# Quadcopter.net
KiCad netlist of a schematic drawn in Altium Designer
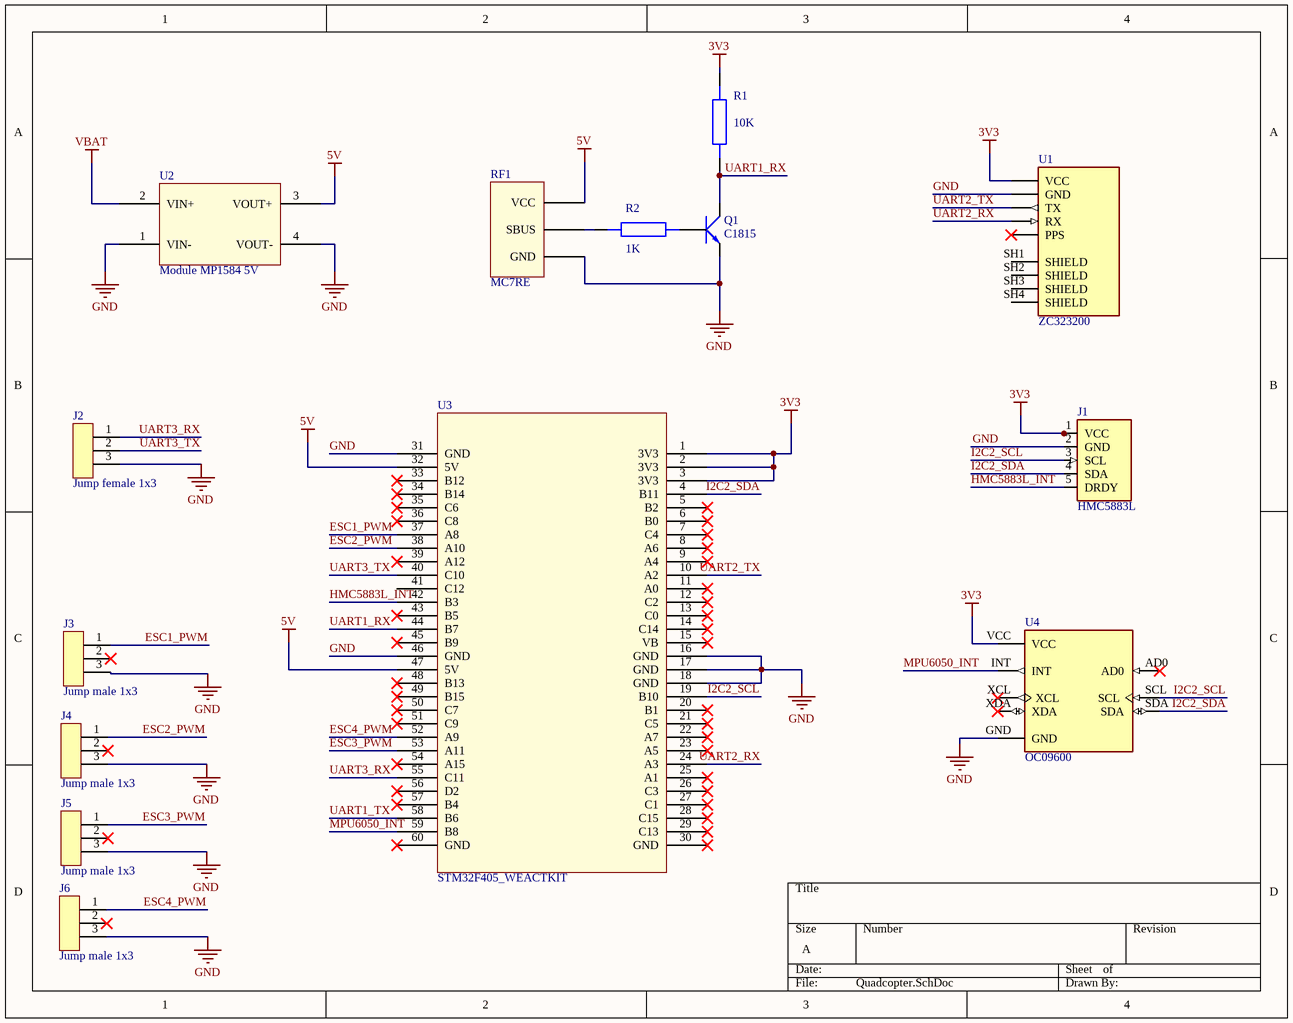
[diagram p0: Quadcopter.SchDoc]

(export (version "E")
  (design (tool "Eeschema 10.0.6"))
  (components
    (comp (ref "J1")
      (value "HMC5883L")
      (footprint "HMC5883L")
      (description "Magnetic Sensor Development Tools 3-Axis Digital Compass w 12-Bit ADC")
      (fields (field (name "MF") "STMicroelectronics"))
      (libsource (lib "Schlib1") (part "HMC5883L"))
    )
    (comp (ref "J2")
      (value "Jump female 1x3")
      (footprint "FEMALE JUMP 1X3")
      (libsource (lib "Schlib1") (part "Jump female 1x3"))
    )
    (comp (ref "J3")
      (value "Jump male 1x3")
      (footprint "FEMALE JUMP 1X3")
      (libsource (lib "Schlib1") (part "Jump male 1x3"))
    )
    (comp (ref "J4")
      (value "Jump male 1x3")
      (footprint "FEMALE JUMP 1X3")
      (libsource (lib "Schlib1") (part "Jump male 1x3"))
    )
    (comp (ref "J5")
      (value "Jump male 1x3")
      (footprint "FEMALE JUMP 1X3")
      (libsource (lib "Schlib1") (part "Jump male 1x3"))
    )
    (comp (ref "J6")
      (value "Jump male 1x3")
      (footprint "FEMALE JUMP 1X3")
      (libsource (lib "Schlib1") (part "Jump male 1x3"))
    )
    (comp (ref "Q1")
      (value "C1815")
      (footprint "TO92127P508H508-3")
      (description "NPN transistor")
      (libsource (lib "Schlib1") (part "Trans C1815 DIP"))
    )
    (comp (ref "R1") (value "10K") (footprint "Tro Vach 1/4W") (libsource (lib "Schlib1") (part "RES")))
    (comp (ref "R2") (value "1K") (footprint "Tro Vach 1/4W") (libsource (lib "Schlib1") (part "RES")))
    (comp (ref "RF1") (value "MC7RE") (footprint "RECEIVER") (libsource (lib "Schlib1") (part "RECEIVER")))
    (comp (ref "U1")
      (value "ZC323200")
      (footprint "GPS_NEO")
      (description "GY-NEO6MV2 GY-GPS6MV2 NEO-6M GPS Module with Flight Control APM2.5")
      (fields (field (name "MF") "YKS"))
      (libsource (lib "Schlib1") (part "ZC323200"))
    )
    (comp (ref "U2")
      (value "Module MP1584 5V")
      (footprint "MODULE_MP1584")
      (libsource (lib "Schlib1") (part "Module MP1584 5V"))
    )
    (comp (ref "U3")
      (value "STM32F405_WEACTKIT")
      (footprint "STM32F405RGT6 - WEACT kit")
      (libsource (lib "Schlib1") (part "STM32F405_WEACTKIT"))
    )
    (comp (ref "U4")
      (value "OC09600")
      (footprint "MODULE_MPU6050")
      (description "GY-521 6 DOF MPU-6050 Module 3 Axis Accelerometer Gyroscope Module for Arduino")
      (fields (field (name "MF") "YKS"))
      (libsource (lib "Schlib1") (part "OC09600"))
    )
  )
  (nets
    (net (code "2") (name "/ESC1_PWM") (class "Default")
      (node (ref "J3") (pin "1") (pintype "passive"))
      (node (ref "U3") (pin "37") (pinfunction "A8_37") (pintype "passive"))
    )
    (net (code "3") (name "/ESC2_PWM") (class "Default")
      (node (ref "J4") (pin "1") (pintype "passive"))
      (node (ref "U3") (pin "38") (pinfunction "A10_38") (pintype "passive"))
    )
    (net (code "4") (name "/ESC3_PWM") (class "Default")
      (node (ref "J5") (pin "1") (pintype "passive"))
      (node (ref "U3") (pin "53") (pinfunction "A11_53") (pintype "passive"))
    )
    (net (code "5") (name "/ESC4_PWM") (class "Default")
      (node (ref "J6") (pin "1") (pintype "passive"))
      (node (ref "U3") (pin "52") (pinfunction "A9_52") (pintype "passive"))
    )
    (net (code "6") (name "/HMC5883L_INT") (class "Default")
      (node (ref "J1") (pin "5") (pinfunction "DRDY_5") (pintype "bidirectional"))
      (node (ref "U3") (pin "42") (pinfunction "B3_42") (pintype "passive"))
    )
    (net (code "7") (name "/I2C2_SCL") (class "Default")
      (node (ref "J1") (pin "3") (pinfunction "SCL_3") (pintype "input"))
      (node (ref "U3") (pin "19") (pinfunction "B10_19") (pintype "passive"))
      (node (ref "U4") (pin "SCL") (pinfunction "SCL_SCL") (pintype "input"))
    )
    (net (code "8") (name "/I2C2_SDA") (class "Default")
      (node (ref "J1") (pin "4") (pinfunction "SDA_4") (pintype "bidirectional"))
      (node (ref "U3") (pin "4") (pinfunction "B11_4") (pintype "passive"))
      (node (ref "U4") (pin "SDA") (pinfunction "SDA_SDA") (pintype "bidirectional"))
    )
    (net (code "9") (name "/MPU6050_INT") (class "Default")
      (node (ref "U3") (pin "59") (pinfunction "B8_59") (pintype "passive"))
      (node (ref "U4") (pin "INT") (pinfunction "INT_INT") (pintype "output"))
    )
    (net (code "10") (name "/UART1_RX") (class "Default")
      (node (ref "Q1") (pin "2") (pinfunction "C_2") (pintype "passive"))
      (node (ref "R1") (pin "1") (pinfunction "1_1") (pintype "passive"))
      (node (ref "U3") (pin "44") (pinfunction "B7_44") (pintype "passive"))
    )
    (net (code "11") (name "/UART1_TX") (class "Default")
      (node (ref "U3") (pin "58") (pinfunction "B6_58") (pintype "passive"))
    )
    (net (code "12") (name "/UART2_RX") (class "Default")
      (node (ref "U1") (pin "2") (pinfunction "RX_2") (pintype "input"))
      (node (ref "U3") (pin "24") (pinfunction "A3_24") (pintype "passive"))
    )
    (net (code "13") (name "/UART2_TX") (class "Default")
      (node (ref "U1") (pin "3") (pinfunction "TX_3") (pintype "output"))
      (node (ref "U3") (pin "10") (pinfunction "A2_10") (pintype "passive"))
    )
    (net (code "14") (name "/UART3_RX") (class "Default")
      (node (ref "J2") (pin "1") (pintype "passive"))
      (node (ref "U3") (pin "55") (pinfunction "C11_55") (pintype "passive"))
    )
    (net (code "15") (name "/UART3_TX") (class "Default")
      (node (ref "J2") (pin "2") (pintype "passive"))
      (node (ref "U3") (pin "40") (pinfunction "C10_40") (pintype "passive"))
    )
    (net (code "16") (name "3V3") (class "Default")
      (node (ref "J1") (pin "1") (pinfunction "VCC_1") (pintype "power_in"))
      (node (ref "R1") (pin "2") (pinfunction "2_2") (pintype "passive"))
      (node (ref "U1") (pin "5") (pinfunction "VCC_5") (pintype "power_in"))
      (node (ref "U3") (pin "1") (pinfunction "3V3_1") (pintype "passive"))
      (node (ref "U3") (pin "2") (pinfunction "3V3_2") (pintype "passive"))
      (node (ref "U3") (pin "3") (pinfunction "3V3_3") (pintype "passive"))
      (node (ref "U4") (pin "VCC") (pinfunction "VCC_VCC") (pintype "power_in"))
    )
    (net (code "17") (name "5V") (class "Default")
      (node (ref "RF1") (pin "5V") (pinfunction "VCC_5V") (pintype "passive"))
      (node (ref "U2") (pin "3") (pinfunction "VOUT+_3") (pintype "passive"))
      (node (ref "U3") (pin "32") (pinfunction "5V_32") (pintype "passive"))
      (node (ref "U3") (pin "47") (pinfunction "5V_47") (pintype "passive"))
    )
    (net (code "18") (name "GND") (class "Default")
      (node (ref "J1") (pin "2") (pinfunction "GND_2") (pintype "power_in"))
      (node (ref "J2") (pin "3") (pintype "passive"))
      (node (ref "J3") (pin "3") (pintype "passive"))
      (node (ref "J4") (pin "3") (pintype "passive"))
      (node (ref "J5") (pin "3") (pintype "passive"))
      (node (ref "J6") (pin "3") (pintype "passive"))
      (node (ref "Q1") (pin "1") (pinfunction "E_1") (pintype "passive"))
      (node (ref "RF1") (pin "GND") (pinfunction "GND_GND") (pintype "passive"))
      (node (ref "U1") (pin "4") (pinfunction "GND_4") (pintype "power_in"))
      (node (ref "U2") (pin "1") (pinfunction "VIN-_1") (pintype "passive"))
      (node (ref "U2") (pin "4") (pinfunction "VOUT-_4") (pintype "passive"))
      (node (ref "U3") (pin "16") (pinfunction "GND_16") (pintype "passive"))
      (node (ref "U3") (pin "17") (pinfunction "GND_17") (pintype "passive"))
      (node (ref "U3") (pin "18") (pinfunction "GND_18") (pintype "passive"))
      (node (ref "U3") (pin "31") (pinfunction "GND_31") (pintype "passive"))
      (node (ref "U3") (pin "46") (pinfunction "GND_46") (pintype "passive"))
      (node (ref "U4") (pin "GND") (pinfunction "GND_GND") (pintype "power_in"))
    )
    (net (code "19") (name "Net-(Q1-B)") (class "Default")
      (node (ref "Q1") (pin "3") (pinfunction "B_3") (pintype "passive"))
      (node (ref "R2") (pin "2") (pinfunction "2_2") (pintype "passive"))
    )
    (net (code "20") (name "Net-(R2-Pad1)") (class "Default")
      (node (ref "R2") (pin "1") (pinfunction "1_1") (pintype "passive"))
      (node (ref "RF1") (pin "SBUS") (pinfunction "SBUS_SBUS") (pintype "passive"))
    )
    (net (code "21") (name "VBAT") (class "Default")
      (node (ref "U2") (pin "2") (pinfunction "VIN+_2") (pintype "passive"))
    )
    (net (code "22") (name "unconnected-(J3-Pad2)") (class "Default")
      (node (ref "J3") (pin "2") (pintype "passive+no_connect"))
    )
    (net (code "23") (name "unconnected-(J4-Pad2)") (class "Default")
      (node (ref "J4") (pin "2") (pintype "passive+no_connect"))
    )
    (net (code "24") (name "unconnected-(J5-Pad2)") (class "Default")
      (node (ref "J5") (pin "2") (pintype "passive+no_connect"))
    )
    (net (code "25") (name "unconnected-(J6-Pad2)") (class "Default")
      (node (ref "J6") (pin "2") (pintype "passive+no_connect"))
    )
    (net (code "26") (name "unconnected-(U1-PPS-Pad1)") (class "Default")
      (node (ref "U1") (pin "1") (pinfunction "PPS_1") (pintype "passive+no_connect"))
    )
    (net (code "27") (name "unconnected-(U1-SHIELD-PadSH1)") (class "Default")
      (node (ref "U1") (pin "SH1") (pinfunction "SHIELD_SH1") (pintype "passive"))
    )
    (net (code "28") (name "unconnected-(U1-SHIELD-PadSH2)") (class "Default")
      (node (ref "U1") (pin "SH2") (pinfunction "SHIELD_SH2") (pintype "passive"))
    )
    (net (code "29") (name "unconnected-(U1-SHIELD-PadSH3)") (class "Default")
      (node (ref "U1") (pin "SH3") (pinfunction "SHIELD_SH3") (pintype "passive"))
    )
    (net (code "30") (name "unconnected-(U1-SHIELD-PadSH4)") (class "Default")
      (node (ref "U1") (pin "SH4") (pinfunction "SHIELD_SH4") (pintype "passive"))
    )
    (net (code "31") (name "unconnected-(U3-A0-Pad11)") (class "Default")
      (node (ref "U3") (pin "11") (pinfunction "A0_11") (pintype "passive+no_connect"))
    )
    (net (code "32") (name "unconnected-(U3-A1-Pad25)") (class "Default")
      (node (ref "U3") (pin "25") (pinfunction "A1_25") (pintype "passive+no_connect"))
    )
    (net (code "33") (name "unconnected-(U3-A4-Pad9)") (class "Default")
      (node (ref "U3") (pin "9") (pinfunction "A4_9") (pintype "passive+no_connect"))
    )
    (net (code "34") (name "unconnected-(U3-A5-Pad23)") (class "Default")
      (node (ref "U3") (pin "23") (pinfunction "A5_23") (pintype "passive+no_connect"))
    )
    (net (code "35") (name "unconnected-(U3-A6-Pad8)") (class "Default")
      (node (ref "U3") (pin "8") (pinfunction "A6_8") (pintype "passive+no_connect"))
    )
    (net (code "36") (name "unconnected-(U3-A7-Pad22)") (class "Default")
      (node (ref "U3") (pin "22") (pinfunction "A7_22") (pintype "passive+no_connect"))
    )
    (net (code "37") (name "unconnected-(U3-A12-Pad39)") (class "Default")
      (node (ref "U3") (pin "39") (pinfunction "A12_39") (pintype "passive+no_connect"))
    )
    (net (code "38") (name "unconnected-(U3-A15-Pad54)") (class "Default")
      (node (ref "U3") (pin "54") (pinfunction "A15_54") (pintype "passive+no_connect"))
    )
    (net (code "39") (name "unconnected-(U3-B0-Pad6)") (class "Default")
      (node (ref "U3") (pin "6") (pinfunction "B0_6") (pintype "passive+no_connect"))
    )
    (net (code "40") (name "unconnected-(U3-B1-Pad20)") (class "Default")
      (node (ref "U3") (pin "20") (pinfunction "B1_20") (pintype "passive+no_connect"))
    )
    (net (code "41") (name "unconnected-(U3-B2-Pad5)") (class "Default")
      (node (ref "U3") (pin "5") (pinfunction "B2_5") (pintype "passive+no_connect"))
    )
    (net (code "42") (name "unconnected-(U3-B4-Pad57)") (class "Default")
      (node (ref "U3") (pin "57") (pinfunction "B4_57") (pintype "passive+no_connect"))
    )
    (net (code "43") (name "unconnected-(U3-B5-Pad43)") (class "Default")
      (node (ref "U3") (pin "43") (pinfunction "B5_43") (pintype "passive+no_connect"))
    )
    (net (code "44") (name "unconnected-(U3-B9-Pad45)") (class "Default")
      (node (ref "U3") (pin "45") (pinfunction "B9_45") (pintype "passive+no_connect"))
    )
    (net (code "45") (name "unconnected-(U3-B12-Pad33)") (class "Default")
      (node (ref "U3") (pin "33") (pinfunction "B12_33") (pintype "passive+no_connect"))
    )
    (net (code "46") (name "unconnected-(U3-B13-Pad48)") (class "Default")
      (node (ref "U3") (pin "48") (pinfunction "B13_48") (pintype "passive+no_connect"))
    )
    (net (code "47") (name "unconnected-(U3-B14-Pad34)") (class "Default")
      (node (ref "U3") (pin "34") (pinfunction "B14_34") (pintype "passive+no_connect"))
    )
    (net (code "48") (name "unconnected-(U3-B15-Pad49)") (class "Default")
      (node (ref "U3") (pin "49") (pinfunction "B15_49") (pintype "passive+no_connect"))
    )
    (net (code "49") (name "unconnected-(U3-C0-Pad13)") (class "Default")
      (node (ref "U3") (pin "13") (pinfunction "C0_13") (pintype "passive+no_connect"))
    )
    (net (code "50") (name "unconnected-(U3-C1-Pad27)") (class "Default")
      (node (ref "U3") (pin "27") (pinfunction "C1_27") (pintype "passive+no_connect"))
    )
    (net (code "51") (name "unconnected-(U3-C2-Pad12)") (class "Default")
      (node (ref "U3") (pin "12") (pinfunction "C2_12") (pintype "passive+no_connect"))
    )
    (net (code "52") (name "unconnected-(U3-C3-Pad26)") (class "Default")
      (node (ref "U3") (pin "26") (pinfunction "C3_26") (pintype "passive+no_connect"))
    )
    (net (code "53") (name "unconnected-(U3-C4-Pad7)") (class "Default")
      (node (ref "U3") (pin "7") (pinfunction "C4_7") (pintype "passive+no_connect"))
    )
    (net (code "54") (name "unconnected-(U3-C5-Pad21)") (class "Default")
      (node (ref "U3") (pin "21") (pinfunction "C5_21") (pintype "passive+no_connect"))
    )
    (net (code "55") (name "unconnected-(U3-C6-Pad35)") (class "Default")
      (node (ref "U3") (pin "35") (pinfunction "C6_35") (pintype "passive+no_connect"))
    )
    (net (code "56") (name "unconnected-(U3-C7-Pad50)") (class "Default")
      (node (ref "U3") (pin "50") (pinfunction "C7_50") (pintype "passive+no_connect"))
    )
    (net (code "57") (name "unconnected-(U3-C8-Pad36)") (class "Default")
      (node (ref "U3") (pin "36") (pinfunction "C8_36") (pintype "passive+no_connect"))
    )
    (net (code "58") (name "unconnected-(U3-C9-Pad51)") (class "Default")
      (node (ref "U3") (pin "51") (pinfunction "C9_51") (pintype "passive+no_connect"))
    )
    (net (code "59") (name "unconnected-(U3-C12-Pad41)") (class "Default")
      (node (ref "U3") (pin "41") (pinfunction "C12_41") (pintype "passive"))
    )
    (net (code "60") (name "unconnected-(U3-C13-Pad29)") (class "Default")
      (node (ref "U3") (pin "29") (pinfunction "C13_29") (pintype "passive+no_connect"))
    )
    (net (code "61") (name "unconnected-(U3-C14-Pad14)") (class "Default")
      (node (ref "U3") (pin "14") (pinfunction "C14_14") (pintype "passive+no_connect"))
    )
    (net (code "62") (name "unconnected-(U3-C15-Pad28)") (class "Default")
      (node (ref "U3") (pin "28") (pinfunction "C15_28") (pintype "passive+no_connect"))
    )
    (net (code "63") (name "unconnected-(U3-D2-Pad56)") (class "Default")
      (node (ref "U3") (pin "56") (pinfunction "D2_56") (pintype "passive+no_connect"))
    )
    (net (code "64") (name "unconnected-(U3-GND-Pad30)") (class "Default")
      (node (ref "U3") (pin "30") (pinfunction "GND_30") (pintype "passive+no_connect"))
    )
    (net (code "65") (name "unconnected-(U3-GND-Pad60)") (class "Default")
      (node (ref "U3") (pin "60") (pinfunction "GND_60") (pintype "passive+no_connect"))
    )
    (net (code "66") (name "unconnected-(U3-VB-Pad15)") (class "Default")
      (node (ref "U3") (pin "15") (pinfunction "VB_15") (pintype "passive+no_connect"))
    )
    (net (code "67") (name "unconnected-(U4-PadAD0)") (class "Default")
      (node (ref "U4") (pin "AD0") (pinfunction "AD0_AD0") (pintype "input+no_connect"))
    )
    (net (code "68") (name "unconnected-(U4-PadXCL)") (class "Default")
      (node (ref "U4") (pin "XCL") (pinfunction "XCL_XCL") (pintype "output+no_connect"))
    )
    (net (code "69") (name "unconnected-(U4-PadXDA)") (class "Default")
      (node (ref "U4") (pin "XDA") (pinfunction "XDA_XDA") (pintype "bidirectional+no_connect"))
    )
  )
)
